# Heart-Earrings_2025-02-14.net
KiCad netlist of a schematic drawn in Altium Designer
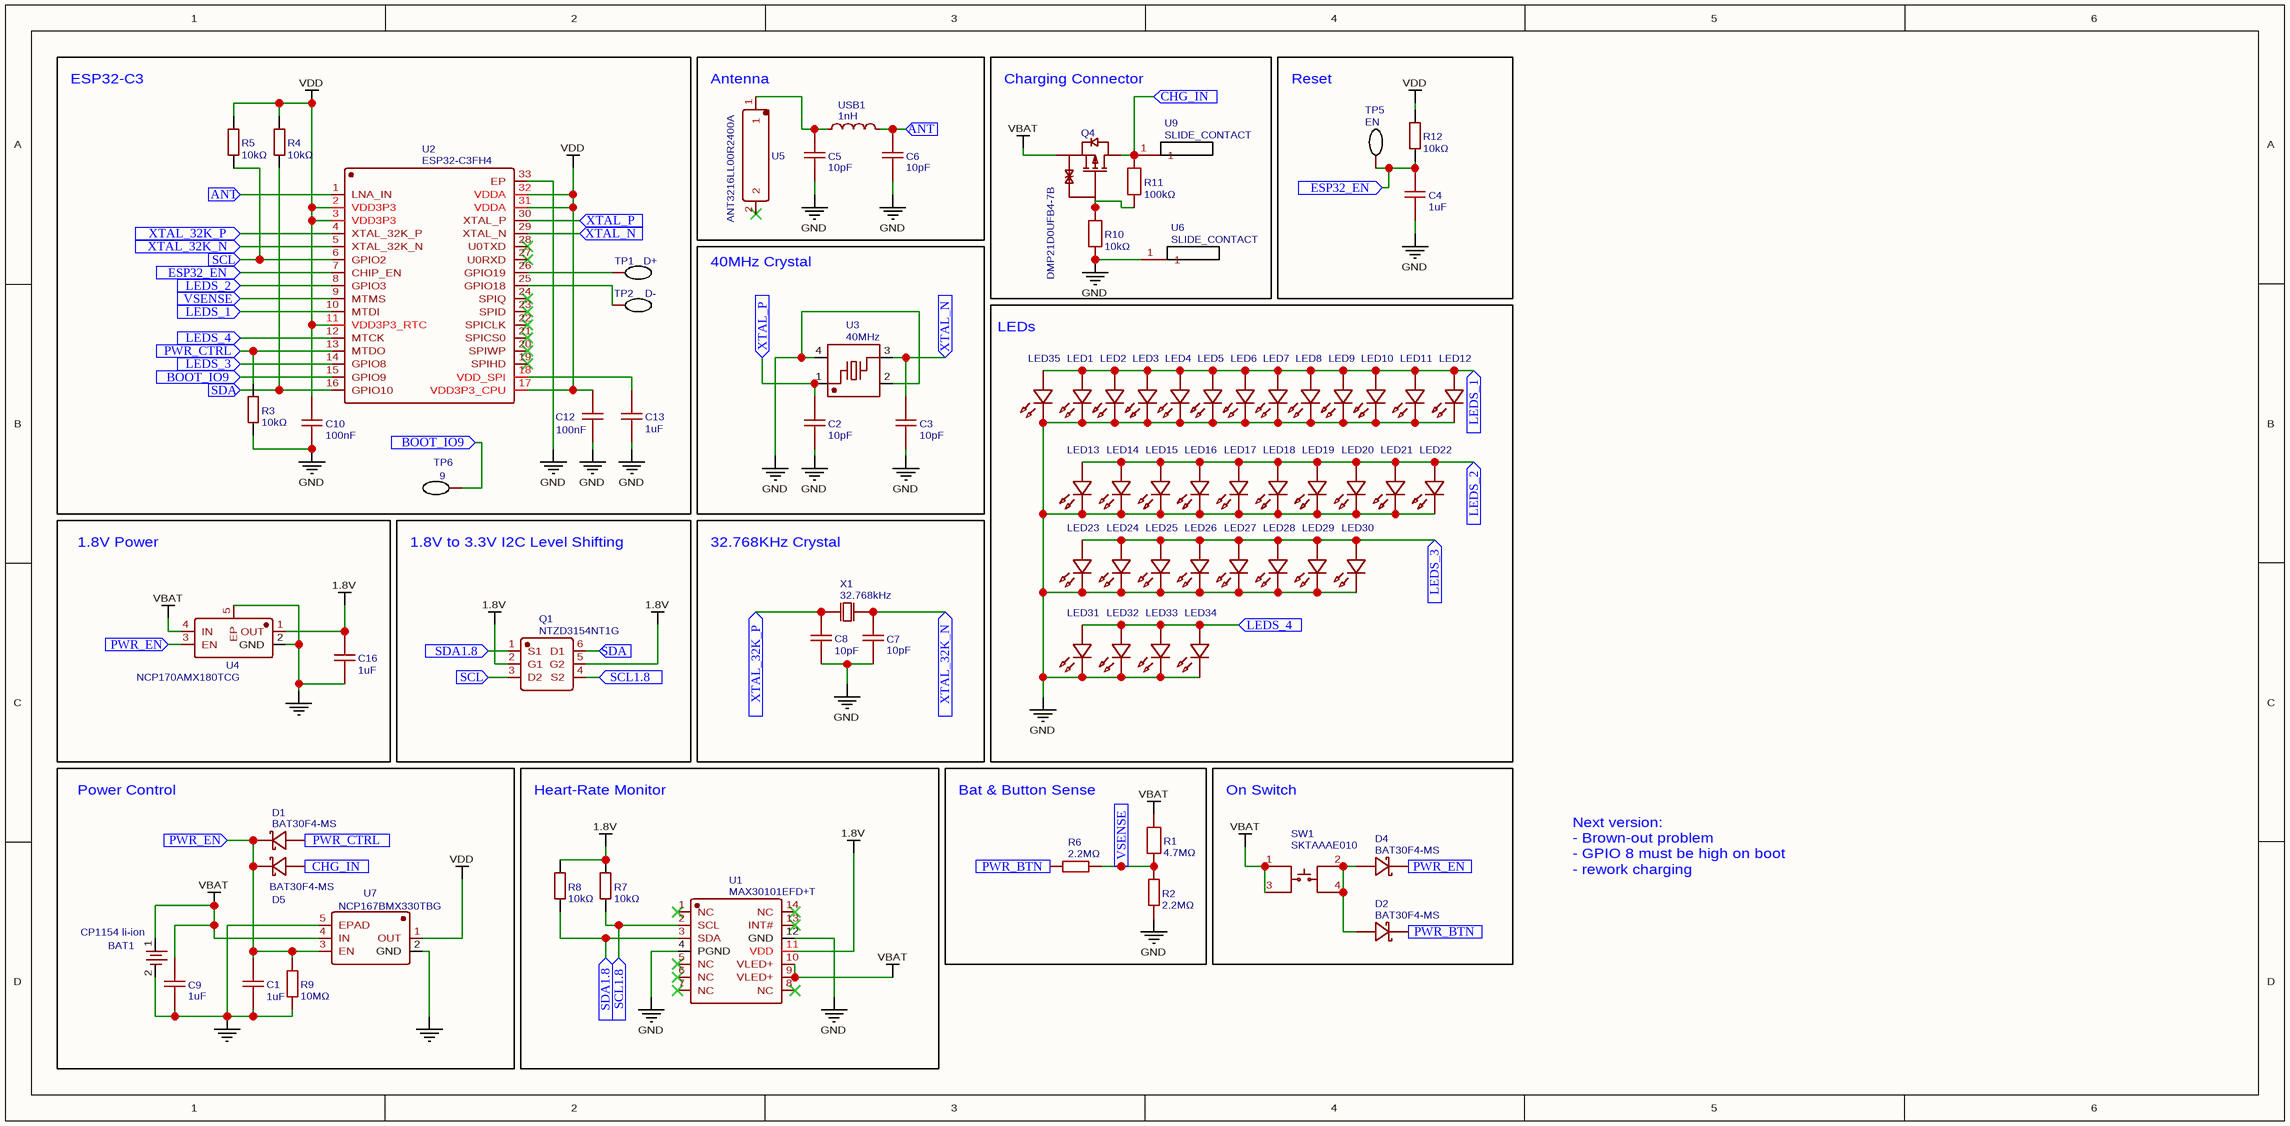
[diagram p0: Heart-Earrings_2025-02-14.schdoc]

(export (version "E")
  (design (tool "Eeschema 10.0.6"))
  (components
    (comp (ref "BAT1")
      (value "CP1154 li-ion")
      (fields
        (field (name "MANUFACTURER") "Varta")
        (field (name "MANUFACTURER PART") "MY-2032-10")
        (field (name "CONTRIBUTOR") "robdobsn")
      )
      (libsource (lib "altium-import") (part "root_3_CP1154 li-ion_"))
    )
    (comp (ref "C1")
      (value "1uF")
      (fields
        (field (name "MANUFACTURER") "SAMSUNG(三星)")
        (field (name "MANUFACTURER PART") "CL05A105KA5NQNC")
      )
      (libsource (lib "altium-import") (part "root_1_1uF_"))
    )
    (comp (ref "C2")
      (value "10pF")
      (fields
        (field (name "MANUFACTURER") "muRata(村田)")
        (field (name "MANUFACTURER PART") "GRM0335C1H100FA01D")
        (field (name "CONTRIBUTOR") "LCSC")
      )
      (libsource (lib "altium-import") (part "root_1_10pF_"))
    )
    (comp (ref "C3")
      (value "10pF")
      (fields
        (field (name "MANUFACTURER") "muRata(村田)")
        (field (name "MANUFACTURER PART") "GRM0335C1H100FA01D")
        (field (name "CONTRIBUTOR") "LCSC")
      )
      (libsource (lib "altium-import") (part "root_1_10pF_"))
    )
    (comp (ref "C4")
      (value "1uF")
      (fields
        (field (name "MANUFACTURER") "SAMSUNG(三星)")
        (field (name "MANUFACTURER PART") "CL05A105KA5NQNC")
      )
      (libsource (lib "altium-import") (part "root_1_1uF_"))
    )
    (comp (ref "C5")
      (value "10pF")
      (fields
        (field (name "MANUFACTURER") "muRata(村田)")
        (field (name "MANUFACTURER PART") "GRM0335C1H100FA01D")
        (field (name "CONTRIBUTOR") "LCSC")
      )
      (libsource (lib "altium-import") (part "root_1_10pF_"))
    )
    (comp (ref "C6")
      (value "10pF")
      (fields
        (field (name "MANUFACTURER") "muRata(村田)")
        (field (name "MANUFACTURER PART") "GRM0335C1H100FA01D")
        (field (name "CONTRIBUTOR") "LCSC")
      )
      (libsource (lib "altium-import") (part "root_1_10pF_"))
    )
    (comp (ref "C7")
      (value "10pF")
      (fields
        (field (name "MANUFACTURER") "muRata(村田)")
        (field (name "MANUFACTURER PART") "GRM0335C1H100FA01D")
        (field (name "CONTRIBUTOR") "LCSC")
      )
      (libsource (lib "altium-import") (part "root_1_10pF_"))
    )
    (comp (ref "C8")
      (value "10pF")
      (fields
        (field (name "MANUFACTURER") "muRata(村田)")
        (field (name "MANUFACTURER PART") "GRM0335C1H100FA01D")
        (field (name "CONTRIBUTOR") "LCSC")
      )
      (libsource (lib "altium-import") (part "root_3_10pF_"))
    )
    (comp (ref "C9")
      (value "1uF")
      (fields
        (field (name "MANUFACTURER") "SAMSUNG(三星)")
        (field (name "MANUFACTURER PART") "CL03A105MP3NSNH")
        (field (name "CONTRIBUTOR") "lcsc")
      )
      (libsource (lib "altium-import") (part "root_1_1uF_"))
    )
    (comp (ref "C10")
      (value "100nF")
      (fields
        (field (name "MANUFACTURER") "muRata(村田)")
        (field (name "MANUFACTURER PART") "GRM033C70J104ME14D")
        (field (name "CONTRIBUTOR") "lcsc")
      )
      (libsource (lib "") (part "root_1_100nF__1"))
    )
    (comp (ref "C12")
      (value "100nF")
      (fields
        (field (name "MANUFACTURER") "SAMSUNG(三星)")
        (field (name "MANUFACTURER PART") "CL05B104KB54PNC")
        (field (name "CONTRIBUTOR") "LCSC")
      )
      (libsource (lib "altium-import") (part "root_1_100nF_"))
    )
    (comp (ref "C13")
      (value "1uF")
      (fields
        (field (name "MANUFACTURER") "SAMSUNG(三星)")
        (field (name "MANUFACTURER PART") "CL05A105KA5NQNC")
      )
      (libsource (lib "altium-import") (part "root_1_1uF_"))
    )
    (comp (ref "C16")
      (value "1uF")
      (fields
        (field (name "MANUFACTURER") "SAMSUNG(三星)")
        (field (name "MANUFACTURER PART") "CL05A105KA5NQNC")
      )
      (libsource (lib "altium-import") (part "root_1_1uF_"))
    )
    (comp (ref "D1")
      (value "BAT30F4-MS")
      (fields (field (name "MANUFACTURER") "MSKSEMI(美森科)") (field (name "CONTRIBUTOR") "lcsc"))
      (libsource (lib "altium-import") (part "root_0_BAT30F4-MS_"))
    )
    (comp (ref "D2")
      (value "BAT30F4-MS")
      (fields (field (name "MANUFACTURER") "MSKSEMI(美森科)") (field (name "CONTRIBUTOR") "lcsc"))
      (libsource (lib "altium-import") (part "root_2_BAT30F4-MS_"))
    )
    (comp (ref "D4")
      (value "BAT30F4-MS")
      (fields (field (name "MANUFACTURER") "MSKSEMI(美森科)") (field (name "CONTRIBUTOR") "lcsc"))
      (libsource (lib "altium-import") (part "root_2_BAT30F4-MS_"))
    )
    (comp (ref "D5")
      (value "BAT30F4-MS")
      (fields (field (name "MANUFACTURER") "MSKSEMI(美森科)") (field (name "CONTRIBUTOR") "lcsc"))
      (libsource (lib "altium-import") (part "root_0_BAT30F4-MS_"))
    )
    (comp (ref "LED1")
      (value "XL-0201SURC")
      (fields (field (name "MANUFACTURER") "XINGLIGHT(成兴光)") (field (name "CONTRIBUTOR") "lcsc"))
      (libsource (lib "altium-import") (part "root_1_XL-0201SURC_"))
    )
    (comp (ref "LED2")
      (value "XL-0201SURC")
      (fields (field (name "MANUFACTURER") "XINGLIGHT(成兴光)") (field (name "CONTRIBUTOR") "lcsc"))
      (libsource (lib "altium-import") (part "root_1_XL-0201SURC_"))
    )
    (comp (ref "LED3")
      (value "XL-0201SURC")
      (fields (field (name "MANUFACTURER") "XINGLIGHT(成兴光)") (field (name "CONTRIBUTOR") "lcsc"))
      (libsource (lib "altium-import") (part "root_1_XL-0201SURC_"))
    )
    (comp (ref "LED4")
      (value "XL-0201SURC")
      (fields (field (name "MANUFACTURER") "XINGLIGHT(成兴光)") (field (name "CONTRIBUTOR") "lcsc"))
      (libsource (lib "altium-import") (part "root_1_XL-0201SURC_"))
    )
    (comp (ref "LED5")
      (value "XL-0201SURC")
      (fields (field (name "MANUFACTURER") "XINGLIGHT(成兴光)") (field (name "CONTRIBUTOR") "lcsc"))
      (libsource (lib "altium-import") (part "root_1_XL-0201SURC_"))
    )
    (comp (ref "LED6")
      (value "XL-0201SURC")
      (fields (field (name "MANUFACTURER") "XINGLIGHT(成兴光)") (field (name "CONTRIBUTOR") "lcsc"))
      (libsource (lib "altium-import") (part "root_1_XL-0201SURC_"))
    )
    (comp (ref "LED7")
      (value "XL-0201SURC")
      (fields (field (name "MANUFACTURER") "XINGLIGHT(成兴光)") (field (name "CONTRIBUTOR") "lcsc"))
      (libsource (lib "altium-import") (part "root_1_XL-0201SURC_"))
    )
    (comp (ref "LED8")
      (value "XL-0201SURC")
      (fields (field (name "MANUFACTURER") "XINGLIGHT(成兴光)") (field (name "CONTRIBUTOR") "lcsc"))
      (libsource (lib "altium-import") (part "root_1_XL-0201SURC_"))
    )
    (comp (ref "LED9")
      (value "XL-0201SURC")
      (fields (field (name "MANUFACTURER") "XINGLIGHT(成兴光)") (field (name "CONTRIBUTOR") "lcsc"))
      (libsource (lib "altium-import") (part "root_1_XL-0201SURC_"))
    )
    (comp (ref "LED10")
      (value "XL-0201SURC")
      (fields (field (name "MANUFACTURER") "XINGLIGHT(成兴光)") (field (name "CONTRIBUTOR") "lcsc"))
      (libsource (lib "altium-import") (part "root_1_XL-0201SURC_"))
    )
    (comp (ref "LED11")
      (value "XL-0201SURC")
      (fields (field (name "MANUFACTURER") "XINGLIGHT(成兴光)") (field (name "CONTRIBUTOR") "lcsc"))
      (libsource (lib "altium-import") (part "root_1_XL-0201SURC_"))
    )
    (comp (ref "LED12")
      (value "XL-0201SURC")
      (fields (field (name "MANUFACTURER") "XINGLIGHT(成兴光)") (field (name "CONTRIBUTOR") "lcsc"))
      (libsource (lib "altium-import") (part "root_1_XL-0201SURC_"))
    )
    (comp (ref "LED13")
      (value "XL-0201SURC")
      (fields (field (name "MANUFACTURER") "XINGLIGHT(成兴光)") (field (name "CONTRIBUTOR") "lcsc"))
      (libsource (lib "altium-import") (part "root_1_XL-0201SURC_"))
    )
    (comp (ref "LED14")
      (value "XL-0201SURC")
      (fields (field (name "MANUFACTURER") "XINGLIGHT(成兴光)") (field (name "CONTRIBUTOR") "lcsc"))
      (libsource (lib "altium-import") (part "root_1_XL-0201SURC_"))
    )
    (comp (ref "LED15")
      (value "XL-0201SURC")
      (fields (field (name "MANUFACTURER") "XINGLIGHT(成兴光)") (field (name "CONTRIBUTOR") "lcsc"))
      (libsource (lib "altium-import") (part "root_1_XL-0201SURC_"))
    )
    (comp (ref "LED16")
      (value "XL-0201SURC")
      (fields (field (name "MANUFACTURER") "XINGLIGHT(成兴光)") (field (name "CONTRIBUTOR") "lcsc"))
      (libsource (lib "altium-import") (part "root_1_XL-0201SURC_"))
    )
    (comp (ref "LED17")
      (value "XL-0201SURC")
      (fields (field (name "MANUFACTURER") "XINGLIGHT(成兴光)") (field (name "CONTRIBUTOR") "lcsc"))
      (libsource (lib "altium-import") (part "root_1_XL-0201SURC_"))
    )
    (comp (ref "LED18")
      (value "XL-0201SURC")
      (fields (field (name "MANUFACTURER") "XINGLIGHT(成兴光)") (field (name "CONTRIBUTOR") "lcsc"))
      (libsource (lib "altium-import") (part "root_1_XL-0201SURC_"))
    )
    (comp (ref "LED19")
      (value "XL-0201SURC")
      (fields (field (name "MANUFACTURER") "XINGLIGHT(成兴光)") (field (name "CONTRIBUTOR") "lcsc"))
      (libsource (lib "altium-import") (part "root_1_XL-0201SURC_"))
    )
    (comp (ref "LED20")
      (value "XL-0201SURC")
      (fields (field (name "MANUFACTURER") "XINGLIGHT(成兴光)") (field (name "CONTRIBUTOR") "lcsc"))
      (libsource (lib "altium-import") (part "root_1_XL-0201SURC_"))
    )
    (comp (ref "LED21")
      (value "XL-0201SURC")
      (fields (field (name "MANUFACTURER") "XINGLIGHT(成兴光)") (field (name "CONTRIBUTOR") "lcsc"))
      (libsource (lib "altium-import") (part "root_1_XL-0201SURC_"))
    )
    (comp (ref "LED22")
      (value "XL-0201SURC")
      (fields (field (name "MANUFACTURER") "XINGLIGHT(成兴光)") (field (name "CONTRIBUTOR") "lcsc"))
      (libsource (lib "altium-import") (part "root_1_XL-0201SURC_"))
    )
    (comp (ref "LED23")
      (value "XL-0201SURC")
      (fields (field (name "MANUFACTURER") "XINGLIGHT(成兴光)") (field (name "CONTRIBUTOR") "lcsc"))
      (libsource (lib "altium-import") (part "root_1_XL-0201SURC_"))
    )
    (comp (ref "LED24")
      (value "XL-0201SURC")
      (fields (field (name "MANUFACTURER") "XINGLIGHT(成兴光)") (field (name "CONTRIBUTOR") "lcsc"))
      (libsource (lib "altium-import") (part "root_1_XL-0201SURC_"))
    )
    (comp (ref "LED25")
      (value "XL-0201SURC")
      (fields (field (name "MANUFACTURER") "XINGLIGHT(成兴光)") (field (name "CONTRIBUTOR") "lcsc"))
      (libsource (lib "altium-import") (part "root_1_XL-0201SURC_"))
    )
    (comp (ref "LED26")
      (value "XL-0201SURC")
      (fields (field (name "MANUFACTURER") "XINGLIGHT(成兴光)") (field (name "CONTRIBUTOR") "lcsc"))
      (libsource (lib "altium-import") (part "root_1_XL-0201SURC_"))
    )
    (comp (ref "LED27")
      (value "XL-0201SURC")
      (fields (field (name "MANUFACTURER") "XINGLIGHT(成兴光)") (field (name "CONTRIBUTOR") "lcsc"))
      (libsource (lib "altium-import") (part "root_1_XL-0201SURC_"))
    )
    (comp (ref "LED28")
      (value "XL-0201SURC")
      (fields (field (name "MANUFACTURER") "XINGLIGHT(成兴光)") (field (name "CONTRIBUTOR") "lcsc"))
      (libsource (lib "altium-import") (part "root_1_XL-0201SURC_"))
    )
    (comp (ref "LED29")
      (value "XL-0201SURC")
      (fields (field (name "MANUFACTURER") "XINGLIGHT(成兴光)") (field (name "CONTRIBUTOR") "lcsc"))
      (libsource (lib "altium-import") (part "root_1_XL-0201SURC_"))
    )
    (comp (ref "LED30")
      (value "XL-0201SURC")
      (fields (field (name "MANUFACTURER") "XINGLIGHT(成兴光)") (field (name "CONTRIBUTOR") "lcsc"))
      (libsource (lib "altium-import") (part "root_1_XL-0201SURC_"))
    )
    (comp (ref "LED31")
      (value "XL-0201SURC")
      (fields (field (name "MANUFACTURER") "XINGLIGHT(成兴光)") (field (name "CONTRIBUTOR") "lcsc"))
      (libsource (lib "altium-import") (part "root_1_XL-0201SURC_"))
    )
    (comp (ref "LED32")
      (value "XL-0201SURC")
      (fields (field (name "MANUFACTURER") "XINGLIGHT(成兴光)") (field (name "CONTRIBUTOR") "lcsc"))
      (libsource (lib "altium-import") (part "root_1_XL-0201SURC_"))
    )
    (comp (ref "LED33")
      (value "XL-0201SURC")
      (fields (field (name "MANUFACTURER") "XINGLIGHT(成兴光)") (field (name "CONTRIBUTOR") "lcsc"))
      (libsource (lib "altium-import") (part "root_1_XL-0201SURC_"))
    )
    (comp (ref "LED34")
      (value "XL-0201SURC")
      (fields (field (name "MANUFACTURER") "XINGLIGHT(成兴光)") (field (name "CONTRIBUTOR") "lcsc"))
      (libsource (lib "altium-import") (part "root_1_XL-0201SURC_"))
    )
    (comp (ref "LED35")
      (value "XL-0201SURC")
      (fields (field (name "MANUFACTURER") "XINGLIGHT(成兴光)") (field (name "CONTRIBUTOR") "lcsc"))
      (libsource (lib "altium-import") (part "root_1_XL-0201SURC_"))
    )
    (comp (ref "Q1")
      (value "NTZD3154NT1G")
      (fields (field (name "MANUFACTURER") "onsemi(安森美)") (field (name "CONTRIBUTOR") "LCSC"))
      (libsource (lib "altium-import") (part "root_0_NTZD3154NT1G_"))
    )
    (comp (ref "Q4")
      (value "DMP21D0UFB4-7B")
      (fields (field (name "MANUFACTURER") "DIODES(美台)") (field (name "CONTRIBUTOR") "LCSC"))
      (libsource (lib "altium-import") (part "root_3_DMP21D0UFB4-7B_"))
    )
    (comp (ref "R1")
      (value "4.7MΩ")
      (fields
        (field (name "MANUFACTURER") "UNI-ROYAL(厚声)")
        (field (name "MANUFACTURER PART") "0402WGF4704TCE")
        (field (name "CONTRIBUTOR") "LCSC")
      )
      (libsource (lib "altium-import") (part "root_1_4.7MΩ_"))
    )
    (comp (ref "R2")
      (value "2.2MΩ")
      (fields
        (field (name "MANUFACTURER") "YAGEO(国巨)")
        (field (name "MANUFACTURER PART") "RC0402JR-072M2L")
        (field (name "CONTRIBUTOR") "LCSC")
      )
      (libsource (lib "altium-import") (part "root_1_2.2MΩ_"))
    )
    (comp (ref "R3")
      (value "10kΩ")
      (fields
        (field (name "MANUFACTURER") "UNI-ROYAL(厚声)")
        (field (name "MANUFACTURER PART") "0402WGF1002TCE")
      )
      (libsource (lib "altium-import") (part "root_1_10kΩ_"))
    )
    (comp (ref "R4")
      (value "10kΩ")
      (fields
        (field (name "MANUFACTURER") "UNI-ROYAL(厚声)")
        (field (name "MANUFACTURER PART") "0402WGF1002TCE")
      )
      (libsource (lib "altium-import") (part "root_1_10kΩ_"))
    )
    (comp (ref "R5")
      (value "10kΩ")
      (fields
        (field (name "MANUFACTURER") "UNI-ROYAL(厚声)")
        (field (name "MANUFACTURER PART") "0402WGF1002TCE")
      )
      (libsource (lib "altium-import") (part "root_1_10kΩ_"))
    )
    (comp (ref "R6")
      (value "2.2MΩ")
      (fields
        (field (name "MANUFACTURER") "YAGEO(国巨)")
        (field (name "MANUFACTURER PART") "RC0402JR-072M2L")
        (field (name "CONTRIBUTOR") "LCSC")
      )
      (libsource (lib "altium-import") (part "root_2_2.2MΩ_"))
    )
    (comp (ref "R7")
      (value "10kΩ")
      (fields
        (field (name "MANUFACTURER") "UNI-ROYAL(厚声)")
        (field (name "MANUFACTURER PART") "0402WGF1002TCE")
      )
      (libsource (lib "altium-import") (part "root_1_10kΩ_"))
    )
    (comp (ref "R8")
      (value "10kΩ")
      (fields
        (field (name "MANUFACTURER") "UNI-ROYAL(厚声)")
        (field (name "MANUFACTURER PART") "0402WGF1002TCE")
      )
      (libsource (lib "altium-import") (part "root_1_10kΩ_"))
    )
    (comp (ref "R9")
      (value "10MΩ")
      (fields
        (field (name "MANUFACTURER") "YAGEO(国巨)")
        (field (name "MANUFACTURER PART") "AC0402JR-0710ML")
        (field (name "CONTRIBUTOR") "LCSC")
      )
      (libsource (lib "altium-import") (part "root_1_10MΩ_"))
    )
    (comp (ref "R10")
      (value "10kΩ")
      (fields
        (field (name "MANUFACTURER") "VISHAY(威世)")
        (field (name "MANUFACTURER PART") "CRCW020110K0FKED")
        (field (name "CONTRIBUTOR") "LCSC")
      )
      (libsource (lib "") (part "root_1_10kΩ__1"))
    )
    (comp (ref "R11")
      (value "100kΩ")
      (fields
        (field (name "MANUFACTURER") "VISHAY(威世)")
        (field (name "MANUFACTURER PART") "CRCW0201100KFKED")
        (field (name "CONTRIBUTOR") "lcsc")
      )
      (libsource (lib "altium-import") (part "root_1_100kΩ_"))
    )
    (comp (ref "R12")
      (value "10kΩ")
      (fields
        (field (name "MANUFACTURER") "UNI-ROYAL(厚声)")
        (field (name "MANUFACTURER PART") "0402WGF1002TCE")
      )
      (libsource (lib "altium-import") (part "root_1_10kΩ_"))
    )
    (comp (ref "SW1")
      (value "SKTAAAE010")
      (fields (field (name "MANUFACTURER") "ALPSALPINE(阿尔卑斯阿尔派)") (field (name "CONTRIBUTOR") "LCSC"))
      (libsource (lib "altium-import") (part "root_0_SKTAAAE010_"))
    )
    (comp (ref "TP1")
      (value "D+")
      (fields (field (name "MANUFACTURER PART") "TESTPAD") (field (name "CONTRIBUTOR") "wenjuntijee"))
      (libsource (lib "altium-import") (part "root_2_D+_"))
    )
    (comp (ref "TP2")
      (value "D-")
      (fields (field (name "MANUFACTURER PART") "TESTPAD") (field (name "CONTRIBUTOR") "wenjuntijee"))
      (libsource (lib "altium-import") (part "root_2_D-_"))
    )
    (comp (ref "TP5")
      (value "EN")
      (fields (field (name "MANUFACTURER PART") "TESTPAD") (field (name "CONTRIBUTOR") "wenjuntijee"))
      (libsource (lib "altium-import") (part "root_3_EN_"))
    )
    (comp (ref "TP6")
      (value "9")
      (fields (field (name "MANUFACTURER PART") "TESTPAD") (field (name "CONTRIBUTOR") "wenjuntijee"))
      (libsource (lib "altium-import") (part "root_0_9_"))
    )
    (comp (ref "U1")
      (value "MAX30101EFD+T")
      (fields (field (name "MANUFACTURER") "MAXIM(美信)") (field (name "CONTRIBUTOR") "LCSC"))
      (libsource (lib "altium-import") (part "root_0_MAX30101EFD+T_"))
    )
    (comp (ref "U2")
      (value "ESP32-C3FH4")
      (fields (field (name "MANUFACTURER") "ESPRESSIF(乐鑫)") (field (name "CONTRIBUTOR") "LCSC"))
      (libsource (lib "altium-import") (part "root_0_ESP32-C3FH4_"))
    )
    (comp (ref "U3")
      (value "40MHz")
      (fields
        (field (name "MANUFACTURER") "JYJE(晶友嘉)")
        (field (name "MANUFACTURER PART") "TJ1140000HYGBC")
        (field (name "CONTRIBUTOR") "lcsc")
      )
      (libsource (lib "altium-import") (part "root_0_40MHz_"))
    )
    (comp (ref "U4")
      (value "NCP170AMX180TCG")
      (fields (field (name "MANUFACTURER") "onsemi(安森美)") (field (name "CONTRIBUTOR") "LCSC"))
      (libsource (lib "altium-import") (part "root_0_NCP170AMX180TCG_"))
    )
    (comp (ref "U5")
      (value "ANT3216LL00R2400A")
      (fields (field (name "MANUFACTURER") "YAGEO(国巨)") (field (name "CONTRIBUTOR") "LCSC"))
      (libsource (lib "altium-import") (part "root_3_ANT3216LL00R2400A_"))
    )
    (comp (ref "U6")
      (value "SLIDE_CONTACT")
      (fields (field (name "CONTRIBUTOR") "robdobsn"))
      (libsource (lib "altium-import") (part "root_2_SLIDE_CONTACT_"))
    )
    (comp (ref "U7")
      (value "NCP167BMX330TBG")
      (fields (field (name "MANUFACTURER") "onsemi(安森美)") (field (name "CONTRIBUTOR") "LCSC"))
      (libsource (lib "altium-import") (part "root_0_NCP167BMX330TBG_"))
    )
    (comp (ref "U9")
      (value "SLIDE_CONTACT")
      (fields (field (name "CONTRIBUTOR") "robdobsn"))
      (libsource (lib "altium-import") (part "root_2_SLIDE_CONTACT_"))
    )
    (comp (ref "USB1")
      (value "1nH")
      (fields
        (field (name "MANUFACTURER") "TDK")
        (field (name "MANUFACTURER PART") "MLG0603P1N0BTD25")
        (field (name "CONTRIBUTOR") "LCSC")
      )
      (libsource (lib "altium-import") (part "root_0_1nH_"))
    )
    (comp (ref "X1")
      (value "32.768kHz")
      (fields
        (field (name "MANUFACTURER") "EPSON(爱普生)")
        (field (name "MANUFACTURER PART") "X1A000121000500")
        (field (name "CONTRIBUTOR") "lcsc")
      )
      (libsource (lib "altium-import") (part "root_2_32.768kHz_"))
    )
  )
  (nets
    (net (code "1") (name "/ANT") (class "Default")
      (node (ref "C6") (pin "2") (pinfunction "2_2") (pintype "passive"))
      (node (ref "U2") (pin "1") (pinfunction "LNA_IN_1") (pintype "passive"))
      (node (ref "USB1") (pin "2") (pinfunction "2_2") (pintype "passive"))
    )
    (net (code "2") (name "/BOOT_IO9") (class "Default")
      (node (ref "TP6") (pin "1") (pinfunction "1_1") (pintype "passive"))
      (node (ref "U2") (pin "15") (pinfunction "GPIO9_15") (pintype "passive"))
    )
    (net (code "3") (name "/CHG_IN") (class "Default")
      (node (ref "D5") (pin "2") (pinfunction "A_2") (pintype "passive"))
      (node (ref "Q4") (pin "3") (pinfunction "D_3") (pintype "passive"))
      (node (ref "R11") (pin "2") (pinfunction "2_2") (pintype "passive"))
      (node (ref "U9") (pin "1") (pinfunction "1_1") (pintype "passive"))
    )
    (net (code "4") (name "/ESP32_EN") (class "Default")
      (node (ref "C4") (pin "2") (pinfunction "2_2") (pintype "passive"))
      (node (ref "R12") (pin "1") (pinfunction "1_1") (pintype "passive"))
      (node (ref "TP5") (pin "1") (pinfunction "1_1") (pintype "passive"))
      (node (ref "U2") (pin "7") (pinfunction "CHIP_EN_7") (pintype "passive"))
    )
    (net (code "5") (name "/LEDS_1") (class "Default")
      (node (ref "LED1") (pin "2") (pinfunction "A_2") (pintype "passive"))
      (node (ref "LED10") (pin "2") (pinfunction "A_2") (pintype "passive"))
      (node (ref "LED11") (pin "2") (pinfunction "A_2") (pintype "passive"))
      (node (ref "LED12") (pin "2") (pinfunction "A_2") (pintype "passive"))
      (node (ref "LED2") (pin "2") (pinfunction "A_2") (pintype "passive"))
      (node (ref "LED3") (pin "2") (pinfunction "A_2") (pintype "passive"))
      (node (ref "LED35") (pin "2") (pinfunction "A_2") (pintype "passive"))
      (node (ref "LED4") (pin "2") (pinfunction "A_2") (pintype "passive"))
      (node (ref "LED5") (pin "2") (pinfunction "A_2") (pintype "passive"))
      (node (ref "LED6") (pin "2") (pinfunction "A_2") (pintype "passive"))
      (node (ref "LED7") (pin "2") (pinfunction "A_2") (pintype "passive"))
      (node (ref "LED8") (pin "2") (pinfunction "A_2") (pintype "passive"))
      (node (ref "LED9") (pin "2") (pinfunction "A_2") (pintype "passive"))
      (node (ref "U2") (pin "10") (pinfunction "MTDI_10") (pintype "passive"))
    )
    (net (code "6") (name "/LEDS_2") (class "Default")
      (node (ref "LED13") (pin "2") (pinfunction "A_2") (pintype "passive"))
      (node (ref "LED14") (pin "2") (pinfunction "A_2") (pintype "passive"))
      (node (ref "LED15") (pin "2") (pinfunction "A_2") (pintype "passive"))
      (node (ref "LED16") (pin "2") (pinfunction "A_2") (pintype "passive"))
      (node (ref "LED17") (pin "2") (pinfunction "A_2") (pintype "passive"))
      (node (ref "LED18") (pin "2") (pinfunction "A_2") (pintype "passive"))
      (node (ref "LED19") (pin "2") (pinfunction "A_2") (pintype "passive"))
      (node (ref "LED20") (pin "2") (pinfunction "A_2") (pintype "passive"))
      (node (ref "LED21") (pin "2") (pinfunction "A_2") (pintype "passive"))
      (node (ref "LED22") (pin "2") (pinfunction "A_2") (pintype "passive"))
      (node (ref "U2") (pin "8") (pinfunction "GPIO3_8") (pintype "passive"))
    )
    (net (code "7") (name "/LEDS_3") (class "Default")
      (node (ref "LED23") (pin "2") (pinfunction "A_2") (pintype "passive"))
      (node (ref "LED24") (pin "2") (pinfunction "A_2") (pintype "passive"))
      (node (ref "LED25") (pin "2") (pinfunction "A_2") (pintype "passive"))
      (node (ref "LED26") (pin "2") (pinfunction "A_2") (pintype "passive"))
      (node (ref "LED27") (pin "2") (pinfunction "A_2") (pintype "passive"))
      (node (ref "LED28") (pin "2") (pinfunction "A_2") (pintype "passive"))
      (node (ref "LED29") (pin "2") (pinfunction "A_2") (pintype "passive"))
      (node (ref "LED30") (pin "2") (pinfunction "A_2") (pintype "passive"))
      (node (ref "U2") (pin "14") (pinfunction "GPIO8_14") (pintype "passive"))
    )
    (net (code "8") (name "/LEDS_4") (class "Default")
      (node (ref "LED31") (pin "2") (pinfunction "A_2") (pintype "passive"))
      (node (ref "LED32") (pin "2") (pinfunction "A_2") (pintype "passive"))
      (node (ref "LED33") (pin "2") (pinfunction "A_2") (pintype "passive"))
      (node (ref "LED34") (pin "2") (pinfunction "A_2") (pintype "passive"))
      (node (ref "U2") (pin "12") (pinfunction "MTCK_12") (pintype "passive"))
    )
    (net (code "9") (name "/PWR_BTN") (class "Default")
      (node (ref "D2") (pin "1") (pinfunction "K_1") (pintype "passive"))
      (node (ref "R6") (pin "2") (pinfunction "2_2") (pintype "passive"))
    )
    (net (code "10") (name "/PWR_CTRL") (class "Default")
      (node (ref "D1") (pin "2") (pinfunction "A_2") (pintype "passive"))
      (node (ref "R3") (pin "2") (pinfunction "2_2") (pintype "passive"))
      (node (ref "U2") (pin "13") (pinfunction "MTDO_13") (pintype "passive"))
    )
    (net (code "11") (name "/PWR_EN") (class "Default")
      (node (ref "C1") (pin "2") (pinfunction "2_2") (pintype "passive"))
      (node (ref "D1") (pin "1") (pinfunction "K_1") (pintype "passive"))
      (node (ref "D4") (pin "1") (pinfunction "K_1") (pintype "passive"))
      (node (ref "D5") (pin "1") (pinfunction "K_1") (pintype "passive"))
      (node (ref "R9") (pin "2") (pinfunction "2_2") (pintype "passive"))
      (node (ref "U4") (pin "3") (pinfunction "EN_3") (pintype "passive"))
      (node (ref "U7") (pin "3") (pinfunction "EN_3") (pintype "passive"))
    )
    (net (code "12") (name "/SCL") (class "Default")
      (node (ref "Q1") (pin "3") (pinfunction "D2_3") (pintype "passive"))
      (node (ref "R5") (pin "1") (pinfunction "1_1") (pintype "passive"))
      (node (ref "U2") (pin "6") (pinfunction "GPIO2_6") (pintype "passive"))
    )
    (net (code "13") (name "/SCL1.8") (class "Default")
      (node (ref "Q1") (pin "4") (pinfunction "S2_4") (pintype "passive"))
      (node (ref "R7") (pin "1") (pinfunction "1_1") (pintype "passive"))
      (node (ref "U1") (pin "2") (pinfunction "SCL_2") (pintype "passive"))
    )
    (net (code "14") (name "/SDA") (class "Default")
      (node (ref "Q1") (pin "6") (pinfunction "D1_6") (pintype "passive"))
      (node (ref "R4") (pin "1") (pinfunction "1_1") (pintype "passive"))
      (node (ref "U2") (pin "16") (pinfunction "GPIO10_16") (pintype "passive"))
    )
    (net (code "15") (name "/SDA1.8") (class "Default")
      (node (ref "Q1") (pin "1") (pinfunction "S1_1") (pintype "passive"))
      (node (ref "R8") (pin "1") (pinfunction "1_1") (pintype "passive"))
      (node (ref "U1") (pin "3") (pinfunction "SDA_3") (pintype "passive"))
    )
    (net (code "16") (name "/VSENSE") (class "Default")
      (node (ref "R1") (pin "1") (pinfunction "1_1") (pintype "passive"))
      (node (ref "R2") (pin "2") (pinfunction "2_2") (pintype "passive"))
      (node (ref "R6") (pin "1") (pinfunction "1_1") (pintype "passive"))
      (node (ref "U2") (pin "9") (pinfunction "MTMS_9") (pintype "passive"))
    )
    (net (code "17") (name "/XTAL_32K_N") (class "Default")
      (node (ref "C7") (pin "2") (pinfunction "2_2") (pintype "passive"))
      (node (ref "U2") (pin "5") (pinfunction "XTAL_32K_N_5") (pintype "passive"))
      (node (ref "X1") (pin "1") (pinfunction "OSC1_1") (pintype "passive"))
    )
    (net (code "18") (name "/XTAL_32K_P") (class "Default")
      (node (ref "C8") (pin "1") (pinfunction "1_1") (pintype "passive"))
      (node (ref "U2") (pin "4") (pinfunction "XTAL_32K_P_4") (pintype "passive"))
      (node (ref "X1") (pin "2") (pinfunction "OSC2_2") (pintype "passive"))
    )
    (net (code "19") (name "/XTAL_N") (class "Default")
      (node (ref "C3") (pin "2") (pinfunction "2_2") (pintype "passive"))
      (node (ref "U2") (pin "29") (pinfunction "XTAL_N_29") (pintype "passive"))
      (node (ref "U3") (pin "3") (pinfunction "3_3") (pintype "passive"))
    )
    (net (code "20") (name "/XTAL_P") (class "Default")
      (node (ref "C2") (pin "2") (pinfunction "2_2") (pintype "passive"))
      (node (ref "U2") (pin "30") (pinfunction "XTAL_P_30") (pintype "passive"))
      (node (ref "U3") (pin "1") (pinfunction "1_1") (pintype "passive"))
    )
    (net (code "21") (name "1.8V") (class "Default")
      (node (ref "C16") (pin "2") (pinfunction "2_2") (pintype "passive"))
      (node (ref "Q1") (pin "2") (pinfunction "G1_2") (pintype "passive"))
      (node (ref "Q1") (pin "5") (pinfunction "G2_5") (pintype "passive"))
      (node (ref "R7") (pin "2") (pinfunction "2_2") (pintype "passive"))
      (node (ref "R8") (pin "2") (pinfunction "2_2") (pintype "passive"))
      (node (ref "U1") (pin "11") (pinfunction "VDD_11") (pintype "passive"))
      (node (ref "U4") (pin "1") (pinfunction "OUT_1") (pintype "passive"))
    )
    (net (code "22") (name "GND") (class "Default")
      (node (ref "BAT1") (pin "2") (pinfunction "BAT-_2") (pintype "passive"))
      (node (ref "C1") (pin "1") (pinfunction "1_1") (pintype "passive"))
      (node (ref "C10") (pin "1") (pinfunction "1_1") (pintype "passive"))
      (node (ref "C12") (pin "1") (pinfunction "1_1") (pintype "passive"))
      (node (ref "C13") (pin "1") (pinfunction "1_1") (pintype "passive"))
      (node (ref "C16") (pin "1") (pinfunction "1_1") (pintype "passive"))
      (node (ref "C2") (pin "1") (pinfunction "1_1") (pintype "passive"))
      (node (ref "C3") (pin "1") (pinfunction "1_1") (pintype "passive"))
      (node (ref "C4") (pin "1") (pinfunction "1_1") (pintype "passive"))
      (node (ref "C5") (pin "1") (pinfunction "1_1") (pintype "passive"))
      (node (ref "C6") (pin "1") (pinfunction "1_1") (pintype "passive"))
      (node (ref "C7") (pin "1") (pinfunction "1_1") (pintype "passive"))
      (node (ref "C8") (pin "2") (pinfunction "2_2") (pintype "passive"))
      (node (ref "C9") (pin "1") (pinfunction "1_1") (pintype "passive"))
      (node (ref "LED1") (pin "1") (pinfunction "K_1") (pintype "passive"))
      (node (ref "LED10") (pin "1") (pinfunction "K_1") (pintype "passive"))
      (node (ref "LED11") (pin "1") (pinfunction "K_1") (pintype "passive"))
      (node (ref "LED12") (pin "1") (pinfunction "K_1") (pintype "passive"))
      (node (ref "LED13") (pin "1") (pinfunction "K_1") (pintype "passive"))
      (node (ref "LED14") (pin "1") (pinfunction "K_1") (pintype "passive"))
      (node (ref "LED15") (pin "1") (pinfunction "K_1") (pintype "passive"))
      (node (ref "LED16") (pin "1") (pinfunction "K_1") (pintype "passive"))
      (node (ref "LED17") (pin "1") (pinfunction "K_1") (pintype "passive"))
      (node (ref "LED18") (pin "1") (pinfunction "K_1") (pintype "passive"))
      (node (ref "LED19") (pin "1") (pinfunction "K_1") (pintype "passive"))
      (node (ref "LED2") (pin "1") (pinfunction "K_1") (pintype "passive"))
      (node (ref "LED20") (pin "1") (pinfunction "K_1") (pintype "passive"))
      (node (ref "LED21") (pin "1") (pinfunction "K_1") (pintype "passive"))
      (node (ref "LED22") (pin "1") (pinfunction "K_1") (pintype "passive"))
      (node (ref "LED23") (pin "1") (pinfunction "K_1") (pintype "passive"))
      (node (ref "LED24") (pin "1") (pinfunction "K_1") (pintype "passive"))
      (node (ref "LED25") (pin "1") (pinfunction "K_1") (pintype "passive"))
      (node (ref "LED26") (pin "1") (pinfunction "K_1") (pintype "passive"))
      (node (ref "LED27") (pin "1") (pinfunction "K_1") (pintype "passive"))
      (node (ref "LED28") (pin "1") (pinfunction "K_1") (pintype "passive"))
      (node (ref "LED29") (pin "1") (pinfunction "K_1") (pintype "passive"))
      (node (ref "LED3") (pin "1") (pinfunction "K_1") (pintype "passive"))
      (node (ref "LED30") (pin "1") (pinfunction "K_1") (pintype "passive"))
      (node (ref "LED31") (pin "1") (pinfunction "K_1") (pintype "passive"))
      (node (ref "LED32") (pin "1") (pinfunction "K_1") (pintype "passive"))
      (node (ref "LED33") (pin "1") (pinfunction "K_1") (pintype "passive"))
      (node (ref "LED34") (pin "1") (pinfunction "K_1") (pintype "passive"))
      (node (ref "LED35") (pin "1") (pinfunction "K_1") (pintype "passive"))
      (node (ref "LED4") (pin "1") (pinfunction "K_1") (pintype "passive"))
      (node (ref "LED5") (pin "1") (pinfunction "K_1") (pintype "passive"))
      (node (ref "LED6") (pin "1") (pinfunction "K_1") (pintype "passive"))
      (node (ref "LED7") (pin "1") (pinfunction "K_1") (pintype "passive"))
      (node (ref "LED8") (pin "1") (pinfunction "K_1") (pintype "passive"))
      (node (ref "LED9") (pin "1") (pinfunction "K_1") (pintype "passive"))
      (node (ref "R10") (pin "1") (pinfunction "1_1") (pintype "passive"))
      (node (ref "R2") (pin "1") (pinfunction "1_1") (pintype "passive"))
      (node (ref "R3") (pin "1") (pinfunction "1_1") (pintype "passive"))
      (node (ref "R9") (pin "1") (pinfunction "1_1") (pintype "passive"))
      (node (ref "U1") (pin "12") (pinfunction "GND_12") (pintype "passive"))
      (node (ref "U1") (pin "4") (pinfunction "PGND_4") (pintype "passive"))
      (node (ref "U2") (pin "33") (pinfunction "EP_33") (pintype "passive"))
      (node (ref "U3") (pin "2") (pinfunction "GND_2") (pintype "passive"))
      (node (ref "U3") (pin "4") (pinfunction "GND_4") (pintype "passive"))
      (node (ref "U4") (pin "2") (pinfunction "GND_2") (pintype "passive"))
      (node (ref "U4") (pin "5") (pinfunction "EP_5") (pintype "passive"))
      (node (ref "U6") (pin "1") (pinfunction "1_1") (pintype "passive"))
      (node (ref "U7") (pin "2") (pinfunction "GND_2") (pintype "passive"))
      (node (ref "U7") (pin "5") (pinfunction "EPAD_5") (pintype "passive"))
    )
    (net (code "23") (name "Net-(C5-Pad2)") (class "Default")
      (node (ref "C5") (pin "2") (pinfunction "2_2") (pintype "passive"))
      (node (ref "U5") (pin "1") (pinfunction "1_1") (pintype "passive"))
      (node (ref "USB1") (pin "1") (pinfunction "1_1") (pintype "passive"))
    )
    (net (code "24") (name "Net-(D2-A)") (class "Default")
      (node (ref "D2") (pin "2") (pinfunction "A_2") (pintype "passive"))
      (node (ref "D4") (pin "2") (pinfunction "A_2") (pintype "passive"))
      (node (ref "SW1") (pin "2") (pinfunction "2_2") (pintype "passive"))
      (node (ref "SW1") (pin "4") (pinfunction "4_4") (pintype "passive"))
    )
    (net (code "25") (name "Net-(Q4-G)") (class "Default")
      (node (ref "Q4") (pin "1") (pinfunction "G_1") (pintype "passive"))
      (node (ref "R10") (pin "2") (pinfunction "2_2") (pintype "passive"))
      (node (ref "R11") (pin "1") (pinfunction "1_1") (pintype "passive"))
    )
    (net (code "26") (name "Net-(U2-GPIO18)") (class "Default")
      (node (ref "TP2") (pin "1") (pinfunction "1_1") (pintype "passive"))
      (node (ref "U2") (pin "25") (pinfunction "GPIO18_25") (pintype "passive"))
    )
    (net (code "27") (name "Net-(U2-GPIO19)") (class "Default")
      (node (ref "TP1") (pin "1") (pinfunction "1_1") (pintype "passive"))
      (node (ref "U2") (pin "26") (pinfunction "GPIO19_26") (pintype "passive"))
    )
    (net (code "28") (name "Net-(U2-VDD_SPI)") (class "Default")
      (node (ref "C13") (pin "2") (pinfunction "2_2") (pintype "passive"))
      (node (ref "U2") (pin "18") (pinfunction "VDD_SPI_18") (pintype "passive"))
    )
    (net (code "29") (name "VBAT") (class "Default")
      (node (ref "BAT1") (pin "1") (pinfunction "BAT+_1") (pintype "passive"))
      (node (ref "C9") (pin "2") (pinfunction "2_2") (pintype "passive"))
      (node (ref "Q4") (pin "2") (pinfunction "S_2") (pintype "passive"))
      (node (ref "R1") (pin "2") (pinfunction "2_2") (pintype "passive"))
      (node (ref "SW1") (pin "1") (pinfunction "1_1") (pintype "passive"))
      (node (ref "SW1") (pin "3") (pinfunction "3_3") (pintype "passive"))
      (node (ref "U1") (pin "10") (pinfunction "VLED+_10") (pintype "passive"))
      (node (ref "U1") (pin "9") (pinfunction "VLED+_9") (pintype "passive"))
      (node (ref "U4") (pin "4") (pinfunction "IN_4") (pintype "passive"))
      (node (ref "U7") (pin "4") (pinfunction "IN_4") (pintype "passive"))
    )
    (net (code "30") (name "VDD") (class "Default")
      (node (ref "C10") (pin "2") (pinfunction "2_2") (pintype "passive"))
      (node (ref "C12") (pin "2") (pinfunction "2_2") (pintype "passive"))
      (node (ref "R12") (pin "2") (pinfunction "2_2") (pintype "passive"))
      (node (ref "R4") (pin "2") (pinfunction "2_2") (pintype "passive"))
      (node (ref "R5") (pin "2") (pinfunction "2_2") (pintype "passive"))
      (node (ref "U2") (pin "11") (pinfunction "VDD3P3_RTC_11") (pintype "passive"))
      (node (ref "U2") (pin "17") (pinfunction "VDD3P3_CPU_17") (pintype "passive"))
      (node (ref "U2") (pin "2") (pinfunction "VDD3P3_2") (pintype "passive"))
      (node (ref "U2") (pin "3") (pinfunction "VDD3P3_3") (pintype "passive"))
      (node (ref "U2") (pin "31") (pinfunction "VDDA_31") (pintype "passive"))
      (node (ref "U2") (pin "32") (pinfunction "VDDA_32") (pintype "passive"))
      (node (ref "U7") (pin "1") (pinfunction "OUT_1") (pintype "passive"))
    )
    (net (code "31") (name "unconnected-(U1-INT#-Pad13)") (class "Default")
      (node (ref "U1") (pin "13") (pinfunction "INT#_13") (pintype "passive+no_connect"))
    )
    (net (code "32") (name "unconnected-(U1-NC-Pad1)") (class "Default")
      (node (ref "U1") (pin "1") (pinfunction "NC_1") (pintype "passive+no_connect"))
    )
    (net (code "33") (name "unconnected-(U1-NC-Pad5)") (class "Default")
      (node (ref "U1") (pin "5") (pinfunction "NC_5") (pintype "passive+no_connect"))
    )
    (net (code "34") (name "unconnected-(U1-NC-Pad6)") (class "Default")
      (node (ref "U1") (pin "6") (pinfunction "NC_6") (pintype "passive+no_connect"))
    )
    (net (code "35") (name "unconnected-(U1-NC-Pad7)") (class "Default")
      (node (ref "U1") (pin "7") (pinfunction "NC_7") (pintype "passive+no_connect"))
    )
    (net (code "36") (name "unconnected-(U1-NC-Pad8)") (class "Default")
      (node (ref "U1") (pin "8") (pinfunction "NC_8") (pintype "passive+no_connect"))
    )
    (net (code "37") (name "unconnected-(U1-NC-Pad14)") (class "Default")
      (node (ref "U1") (pin "14") (pinfunction "NC_14") (pintype "passive+no_connect"))
    )
    (net (code "38") (name "unconnected-(U2-SPICLK-Pad22)") (class "Default")
      (node (ref "U2") (pin "22") (pinfunction "SPICLK_22") (pintype "passive+no_connect"))
    )
    (net (code "39") (name "unconnected-(U2-SPICS0-Pad21)") (class "Default")
      (node (ref "U2") (pin "21") (pinfunction "SPICS0_21") (pintype "passive+no_connect"))
    )
    (net (code "40") (name "unconnected-(U2-SPID-Pad23)") (class "Default")
      (node (ref "U2") (pin "23") (pinfunction "SPID_23") (pintype "passive+no_connect"))
    )
    (net (code "41") (name "unconnected-(U2-SPIHD-Pad19)") (class "Default")
      (node (ref "U2") (pin "19") (pinfunction "SPIHD_19") (pintype "passive+no_connect"))
    )
    (net (code "42") (name "unconnected-(U2-SPIQ-Pad24)") (class "Default")
      (node (ref "U2") (pin "24") (pinfunction "SPIQ_24") (pintype "passive+no_connect"))
    )
    (net (code "43") (name "unconnected-(U2-SPIWP-Pad20)") (class "Default")
      (node (ref "U2") (pin "20") (pinfunction "SPIWP_20") (pintype "passive+no_connect"))
    )
    (net (code "44") (name "unconnected-(U2-U0RXD-Pad27)") (class "Default")
      (node (ref "U2") (pin "27") (pinfunction "U0RXD_27") (pintype "passive+no_connect"))
    )
    (net (code "45") (name "unconnected-(U2-U0TXD-Pad28)") (class "Default")
      (node (ref "U2") (pin "28") (pinfunction "U0TXD_28") (pintype "passive+no_connect"))
    )
    (net (code "46") (name "unconnected-(U5-Pad2)") (class "Default")
      (node (ref "U5") (pin "2") (pinfunction "2_2") (pintype "passive+no_connect"))
    )
  )
)
